# comms_robot.net
KiCad netlist of a schematic drawn in EAGLE
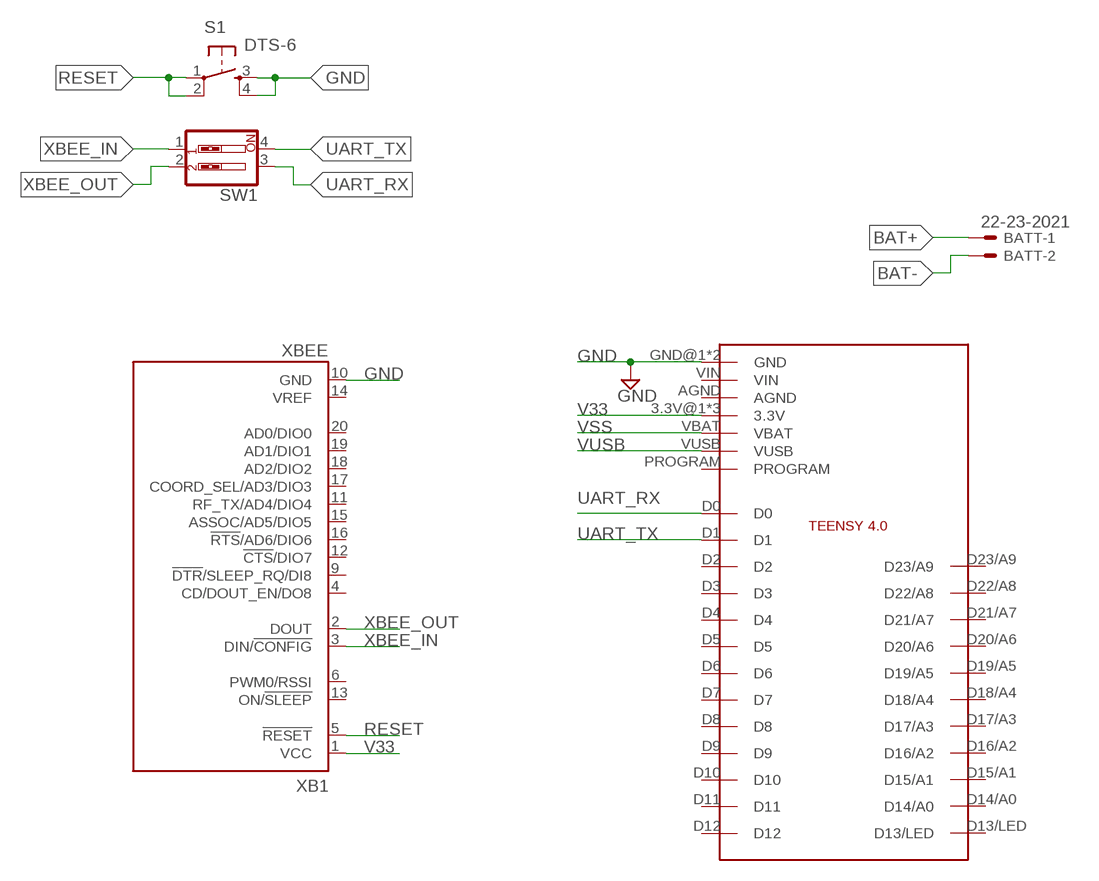
[diagram p0: schematic, sheet 1]

(export (version "E")
  (design (tool "Eeschema 10.0.6"))
  (components
    (comp (ref "BATT")
      (value "22-23-2021")
      (footprint "eagle-import:22-23-2021")
      (fields (field (name "MF") "MOLEX"))
      (libsource (lib "eagle-import") (part "22-23-2021"))
    )
    (comp (ref "S1")
      (value "DTS-6")
      (footprint "eagle-import:DTS-6")
      (libsource (lib "eagle-import") (part "DTS-6"))
    )
    (comp (ref "SW1")
      (value "SW_DIP-2")
      (footprint "eagle-import:EDG-02")
      (libsource (lib "eagle-import") (part "SW_DIP-2"))
    )
    (comp (ref "U$1")
      (value "TEENSY4.0")
      (footprint "eagle-import:TEENSY4.0")
      (libsource (lib "eagle-import") (part "TEENSY4.0"))
    )
    (comp (ref "XB1")
      (value "XBEE")
      (footprint "eagle-import:XBEE")
      (fields (field (name "MPN") "XBP24-Z7UIT-004"))
      (libsource (lib "eagle-import") (part "XBEE"))
    )
  )
  (nets
    (net (code "1") (name "/V33") (class "Default")
      (node (ref "U$1") (pin "3.3V@1") (pinfunction "3.3V_3.3V@1") (pintype "bidirectional"))
      (node (ref "U$1") (pin "3.3V@2") (pinfunction "3.3V_3.3V@2") (pintype "bidirectional"))
      (node (ref "U$1") (pin "ON/OFF") (pinfunction "3.3V_ON/OFF") (pintype "bidirectional"))
      (node (ref "XB1") (pin "1") (pinfunction "VCC_1") (pintype "power_in"))
    )
    (net (code "2") (name "/VSS") (class "Default")
      (node (ref "U$1") (pin "VBAT") (pinfunction "VBAT_VBAT") (pintype "bidirectional"))
    )
    (net (code "3") (name "/VUSB") (class "Default")
      (node (ref "U$1") (pin "VUSB") (pinfunction "VUSB_VUSB") (pintype "bidirectional"))
    )
    (net (code "4") (name "BAT+") (class "Default")
      (node (ref "BATT") (pin "1") (pinfunction "S_1") (pintype "passive"))
    )
    (net (code "5") (name "BAT-") (class "Default")
      (node (ref "BATT") (pin "2") (pinfunction "S_2") (pintype "passive"))
    )
    (net (code "6") (name "GND") (class "Default")
      (node (ref "S1") (pin "3") (pinfunction "3_3") (pintype "passive"))
      (node (ref "S1") (pin "4") (pinfunction "4_4") (pintype "passive"))
      (node (ref "U$1") (pin "GND@1") (pinfunction "GND_GND@1") (pintype "bidirectional"))
      (node (ref "U$1") (pin "GND@2") (pinfunction "GND_GND@2") (pintype "bidirectional"))
      (node (ref "XB1") (pin "10") (pinfunction "GND_10") (pintype "power_in"))
    )
    (net (code "7") (name "RESET") (class "Default")
      (node (ref "S1") (pin "1") (pinfunction "1_1") (pintype "passive"))
      (node (ref "S1") (pin "2") (pinfunction "2_2") (pintype "passive"))
      (node (ref "XB1") (pin "5") (pinfunction "~{RESET}_5") (pintype "input"))
    )
    (net (code "8") (name "UART_RX") (class "Default")
      (node (ref "SW1") (pin "3") (pinfunction "3_3") (pintype "passive"))
      (node (ref "U$1") (pin "D0") (pinfunction "D0_D0") (pintype "bidirectional"))
    )
    (net (code "9") (name "UART_TX") (class "Default")
      (node (ref "SW1") (pin "4") (pinfunction "4_4") (pintype "passive"))
      (node (ref "U$1") (pin "D1") (pinfunction "D1_D1") (pintype "bidirectional"))
    )
    (net (code "10") (name "XBEE_IN") (class "Default")
      (node (ref "SW1") (pin "1") (pinfunction "1_1") (pintype "passive"))
      (node (ref "XB1") (pin "3") (pinfunction "DIN/~{CONFIG}_3") (pintype "input"))
    )
    (net (code "11") (name "XBEE_OUT") (class "Default")
      (node (ref "SW1") (pin "2") (pinfunction "2_2") (pintype "passive"))
      (node (ref "XB1") (pin "2") (pinfunction "DOUT_2") (pintype "output"))
    )
    (net (code "12") (name "unconnected-(U$1-PadAGND)") (class "Default")
      (node (ref "U$1") (pin "AGND") (pinfunction "AGND_AGND") (pintype "bidirectional"))
    )
    (net (code "13") (name "unconnected-(U$1-PadD2)") (class "Default")
      (node (ref "U$1") (pin "D2") (pinfunction "D2_D2") (pintype "bidirectional"))
    )
    (net (code "14") (name "unconnected-(U$1-PadD3)") (class "Default")
      (node (ref "U$1") (pin "D3") (pinfunction "D3_D3") (pintype "bidirectional"))
    )
    (net (code "15") (name "unconnected-(U$1-PadD4)") (class "Default")
      (node (ref "U$1") (pin "D4") (pinfunction "D4_D4") (pintype "bidirectional"))
    )
    (net (code "16") (name "unconnected-(U$1-PadD5)") (class "Default")
      (node (ref "U$1") (pin "D5") (pinfunction "D5_D5") (pintype "bidirectional"))
    )
    (net (code "17") (name "unconnected-(U$1-PadD6)") (class "Default")
      (node (ref "U$1") (pin "D6") (pinfunction "D6_D6") (pintype "bidirectional"))
    )
    (net (code "18") (name "unconnected-(U$1-PadD7)") (class "Default")
      (node (ref "U$1") (pin "D7") (pinfunction "D7_D7") (pintype "bidirectional"))
    )
    (net (code "19") (name "unconnected-(U$1-PadD8)") (class "Default")
      (node (ref "U$1") (pin "D8") (pinfunction "D8_D8") (pintype "bidirectional"))
    )
    (net (code "20") (name "unconnected-(U$1-PadD9)") (class "Default")
      (node (ref "U$1") (pin "D9") (pinfunction "D9_D9") (pintype "bidirectional"))
    )
    (net (code "21") (name "unconnected-(U$1-PadD10)") (class "Default")
      (node (ref "U$1") (pin "D10") (pinfunction "D10_D10") (pintype "bidirectional"))
    )
    (net (code "22") (name "unconnected-(U$1-PadD11)") (class "Default")
      (node (ref "U$1") (pin "D11") (pinfunction "D11_D11") (pintype "bidirectional"))
    )
    (net (code "23") (name "unconnected-(U$1-PadD12)") (class "Default")
      (node (ref "U$1") (pin "D12") (pinfunction "D12_D12") (pintype "bidirectional"))
    )
    (net (code "24") (name "unconnected-(U$1-PadD13{slash}LED)") (class "Default")
      (node (ref "U$1") (pin "D13/LED") (pinfunction "D13/LED_D13/LED") (pintype "bidirectional"))
    )
    (net (code "25") (name "unconnected-(U$1-PadD14{slash}A0)") (class "Default")
      (node (ref "U$1") (pin "D14/A0") (pinfunction "D14/A0_D14/A0") (pintype "bidirectional"))
    )
    (net (code "26") (name "unconnected-(U$1-PadD15{slash}A1)") (class "Default")
      (node (ref "U$1") (pin "D15/A1") (pinfunction "D15/A1_D15/A1") (pintype "bidirectional"))
    )
    (net (code "27") (name "unconnected-(U$1-PadD16{slash}A2)") (class "Default")
      (node (ref "U$1") (pin "D16/A2") (pinfunction "D16/A2_D16/A2") (pintype "bidirectional"))
    )
    (net (code "28") (name "unconnected-(U$1-PadD17{slash}A3)") (class "Default")
      (node (ref "U$1") (pin "D17/A3") (pinfunction "D17/A3_D17/A3") (pintype "bidirectional"))
    )
    (net (code "29") (name "unconnected-(U$1-PadD18{slash}A4)") (class "Default")
      (node (ref "U$1") (pin "D18/A4") (pinfunction "D18/A4_D18/A4") (pintype "bidirectional"))
    )
    (net (code "30") (name "unconnected-(U$1-PadD19{slash}A5)") (class "Default")
      (node (ref "U$1") (pin "D19/A5") (pinfunction "D19/A5_D19/A5") (pintype "bidirectional"))
    )
    (net (code "31") (name "unconnected-(U$1-PadD20{slash}A6)") (class "Default")
      (node (ref "U$1") (pin "D20/A6") (pinfunction "D20/A6_D20/A6") (pintype "bidirectional"))
    )
    (net (code "32") (name "unconnected-(U$1-PadD21{slash}A7)") (class "Default")
      (node (ref "U$1") (pin "D21/A7") (pinfunction "D21/A7_D21/A7") (pintype "bidirectional"))
    )
    (net (code "33") (name "unconnected-(U$1-PadD22{slash}A8)") (class "Default")
      (node (ref "U$1") (pin "D22/A8") (pinfunction "D22/A8_D22/A8") (pintype "bidirectional"))
    )
    (net (code "34") (name "unconnected-(U$1-PadD23{slash}A9)") (class "Default")
      (node (ref "U$1") (pin "D23/A9") (pinfunction "D23/A9_D23/A9") (pintype "bidirectional"))
    )
    (net (code "35") (name "unconnected-(U$1-PadPROGRAM)") (class "Default")
      (node (ref "U$1") (pin "PROGRAM") (pinfunction "PROGRAM_PROGRAM") (pintype "bidirectional"))
    )
    (net (code "36") (name "unconnected-(U$1-PadVIN)") (class "Default")
      (node (ref "U$1") (pin "VIN") (pinfunction "VIN_VIN") (pintype "bidirectional"))
    )
    (net (code "37") (name "unconnected-(XB1-AD0{slash}DIO0-Pad20)") (class "Default")
      (node (ref "XB1") (pin "20") (pinfunction "AD0/DIO0_20") (pintype "bidirectional"))
    )
    (net (code "38") (name "unconnected-(XB1-AD1{slash}DIO1-Pad19)") (class "Default")
      (node (ref "XB1") (pin "19") (pinfunction "AD1/DIO1_19") (pintype "bidirectional"))
    )
    (net (code "39") (name "unconnected-(XB1-AD2{slash}DIO2-Pad18)") (class "Default")
      (node (ref "XB1") (pin "18") (pinfunction "AD2/DIO2_18") (pintype "bidirectional"))
    )
    (net (code "40") (name "unconnected-(XB1-ASSOC{slash}AD5{slash}DIO5-Pad15)") (class "Default")
      (node (ref "XB1") (pin "15") (pinfunction "ASSOC/AD5/DIO5_15") (pintype "bidirectional"))
    )
    (net (code "41") (name "unconnected-(XB1-CD{slash}DOUT_EN{slash}DO8-Pad4)") (class "Default")
      (node (ref "XB1") (pin "4") (pinfunction "CD/DOUT_EN/DO8_4") (pintype "output"))
    )
    (net (code "42") (name "unconnected-(XB1-COORD_SEL{slash}AD3{slash}DIO3-Pad17)") (class "Default")
      (node (ref "XB1") (pin "17") (pinfunction "COORD_SEL/AD3/DIO3_17") (pintype "bidirectional"))
    )
    (net (code "43") (name "unconnected-(XB1-ON{slash}~{SLEEP}-Pad13)") (class "Default")
      (node (ref "XB1") (pin "13") (pinfunction "ON/~{SLEEP}_13") (pintype "output"))
    )
    (net (code "44") (name "unconnected-(XB1-PWM0{slash}RSSI-Pad6)") (class "Default")
      (node (ref "XB1") (pin "6") (pinfunction "PWM0/RSSI_6") (pintype "output"))
    )
    (net (code "45") (name "unconnected-(XB1-RF_TX{slash}AD4{slash}DIO4-Pad11)") (class "Default")
      (node (ref "XB1") (pin "11") (pinfunction "RF_TX/AD4/DIO4_11") (pintype "bidirectional"))
    )
    (net (code "46") (name "unconnected-(XB1-VREF-Pad14)") (class "Default")
      (node (ref "XB1") (pin "14") (pinfunction "VREF_14") (pintype "input"))
    )
    (net (code "47") (name "unconnected-(XB1-~{CTS}{slash}DIO7-Pad12)") (class "Default")
      (node (ref "XB1") (pin "12") (pinfunction "~{CTS}/DIO7_12") (pintype "bidirectional"))
    )
    (net (code "48") (name "unconnected-(XB1-~{DTR}{slash}SLEEP_RQ{slash}DI8-Pad9)") (class "Default")
      (node (ref "XB1") (pin "9") (pinfunction "~{DTR}/SLEEP_RQ/DI8_9") (pintype "bidirectional"))
    )
    (net (code "49") (name "unconnected-(XB1-~{RTS}{slash}AD6{slash}DIO6-Pad16)") (class "Default")
      (node (ref "XB1") (pin "16") (pinfunction "~{RTS}/AD6/DIO6_16") (pintype "bidirectional"))
    )
  )
)
